# motion_sensor2.net
KiCad netlist of a schematic drawn in EasyEDA
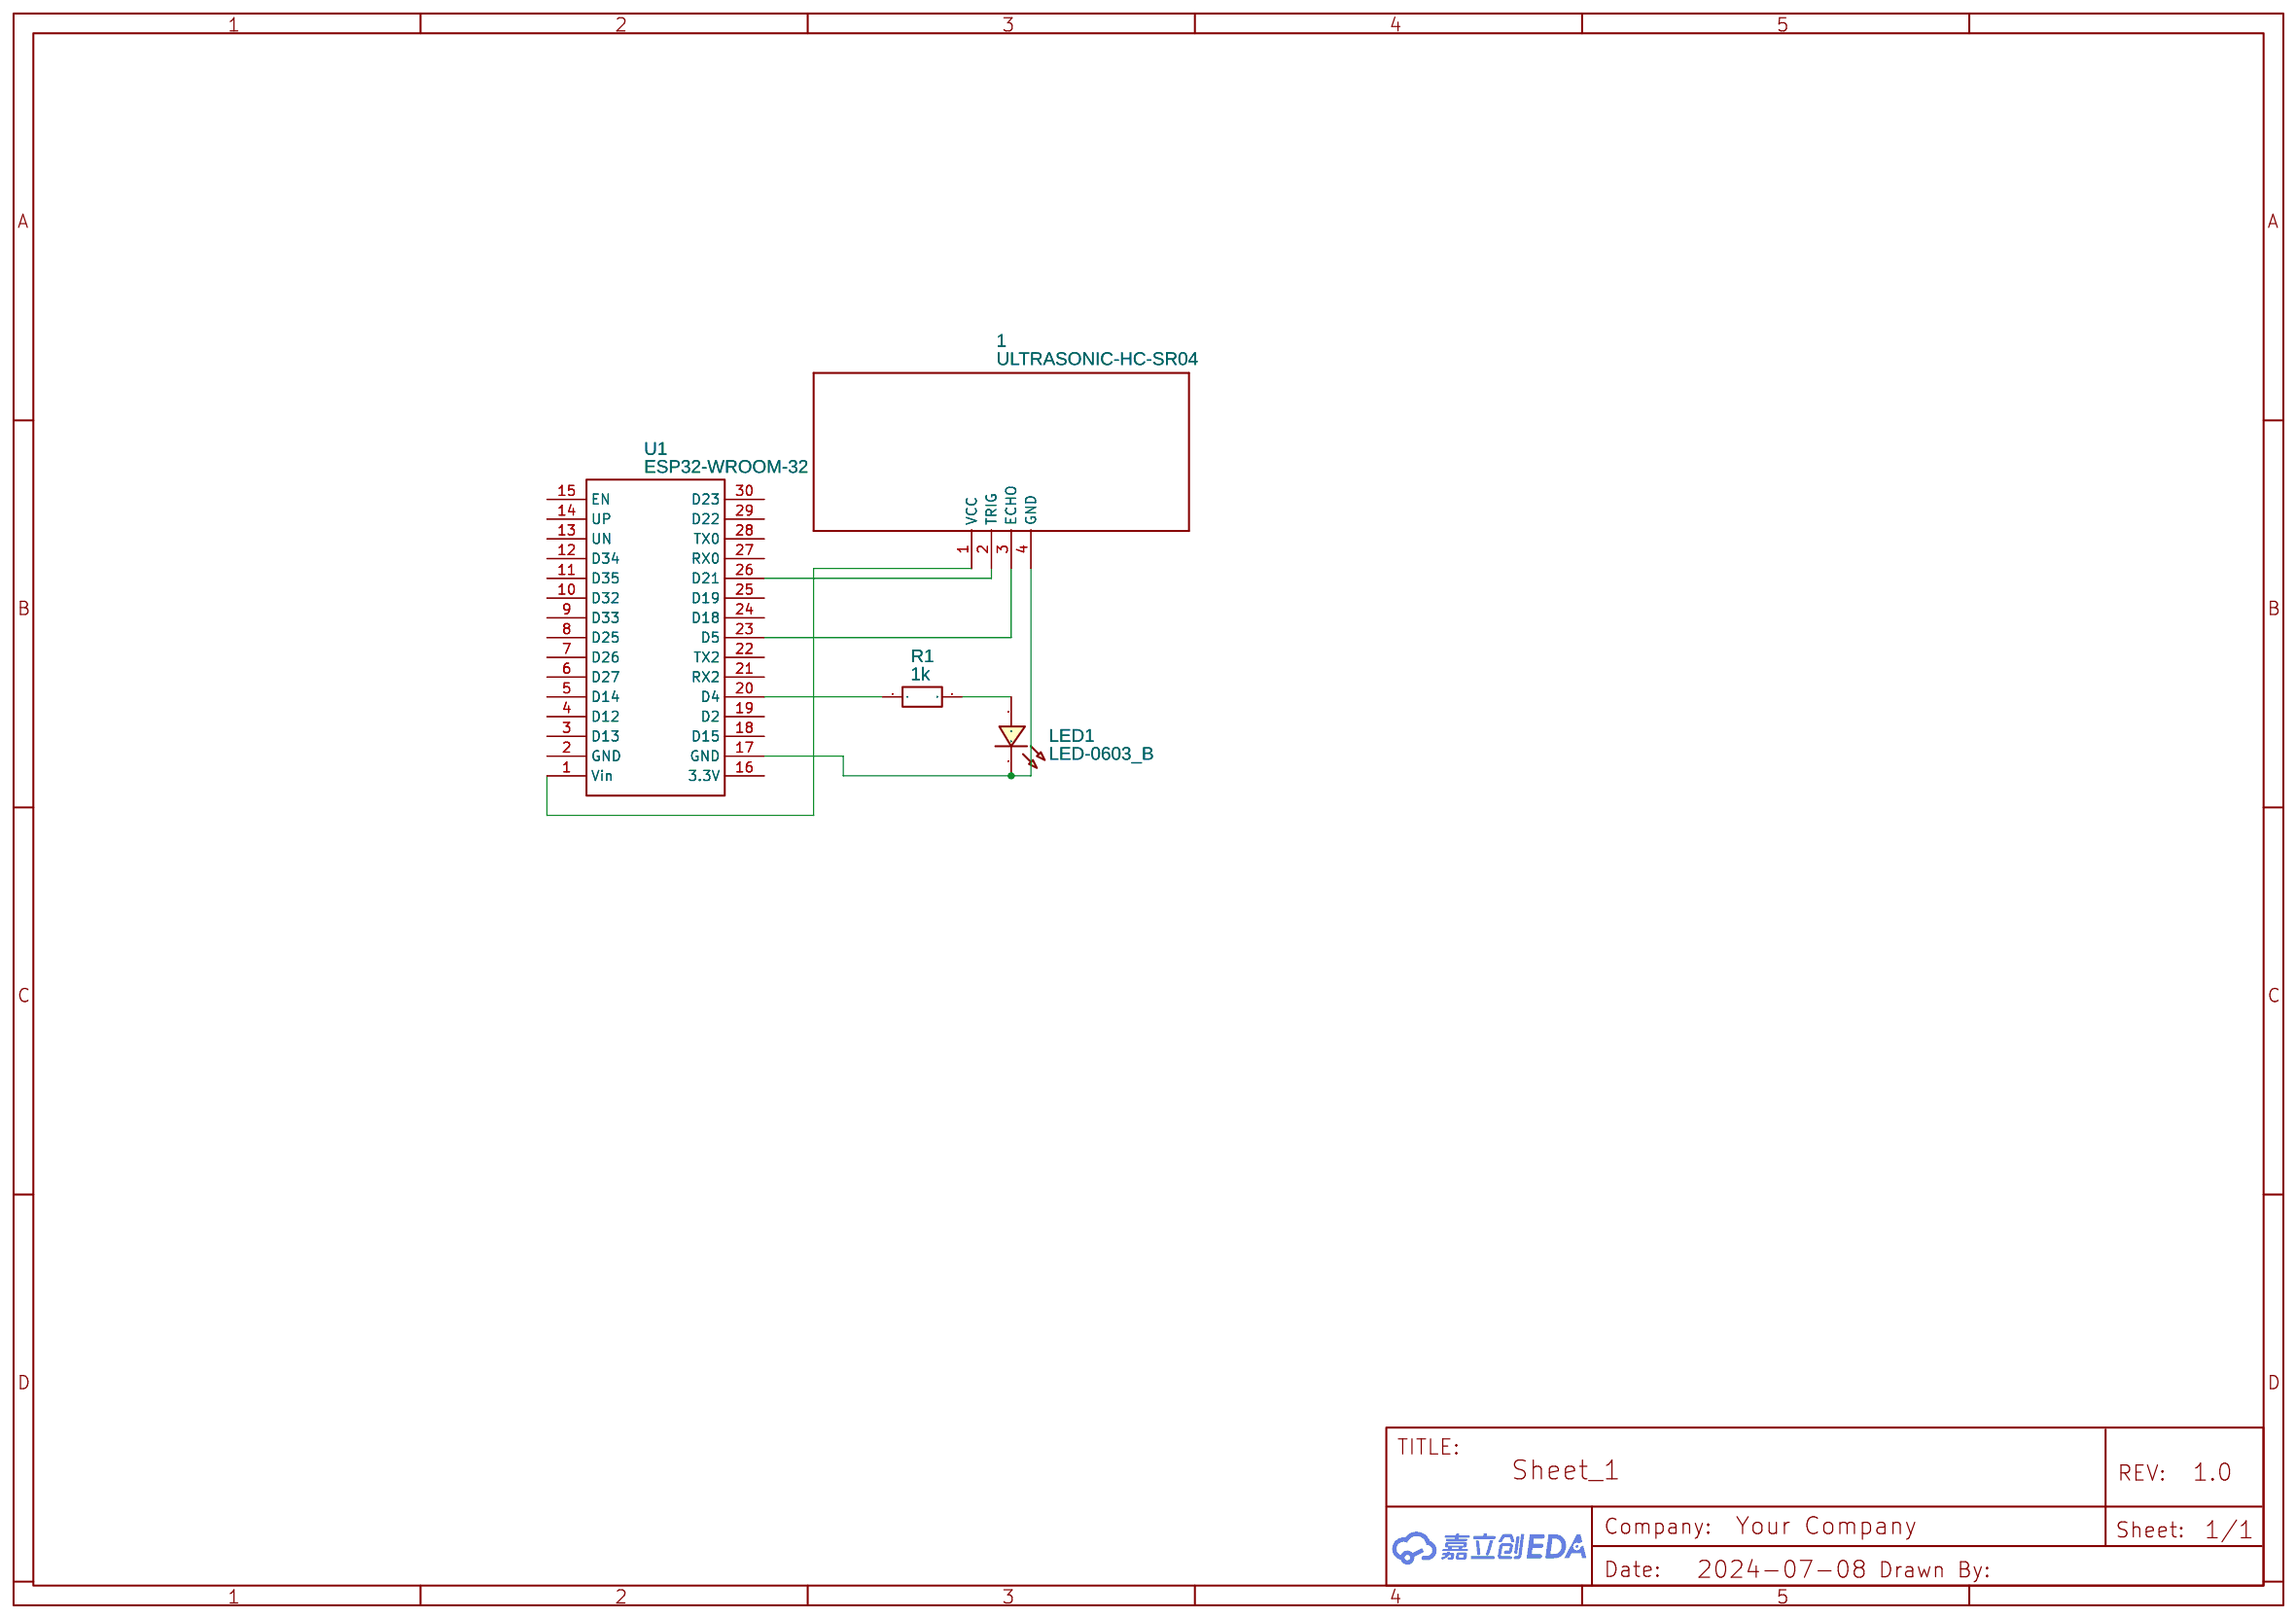
[diagram p0: schematic sheet]

(export (version "E")
  (design (tool "Eeschema 10.0.6"))
  (components
    (comp (ref "1") (value "ULTRASONIC-HC-SR04") (libsource (lib "") (part "ULTRASONIC-HC-SR04")))
    (comp (ref "LED1")
      (value "LED-0603_B")
      (fields
        (field (name "BOM_Manufacturer Part") "19-217/BHC-ZL1M2RY/3T")
        (field (name "BOM_Supplier Part") "C72041")
      )
      (libsource (lib "") (part "LED-0603_B"))
    )
    (comp (ref "R1") (value "1k") (libsource (lib "") (part "R_0603_EU")))
    (comp (ref "U1") (value "ESP32-WROOM-32") (libsource (lib "") (part "ESP32-WROOM-32")))
  )
  (nets
    (net (code "1") (name "Net-(1-ECHO)") (class "Default")
      (node (ref "1") (pin "3") (pinfunction "ECHO_3") (pintype "bidirectional"))
      (node (ref "U1") (pin "23") (pinfunction "D5_23") (pintype "unspecified"))
    )
    (net (code "2") (name "Net-(1-GND)") (class "Default")
      (node (ref "1") (pin "4") (pinfunction "GND_4") (pintype "bidirectional"))
      (node (ref "LED1") (pin "2") (pinfunction "2_2") (pintype "unspecified"))
      (node (ref "U1") (pin "17") (pinfunction "GND_17") (pintype "unspecified"))
    )
    (net (code "3") (name "Net-(1-TRIG)") (class "Default")
      (node (ref "1") (pin "2") (pinfunction "TRIG_2") (pintype "bidirectional"))
      (node (ref "U1") (pin "26") (pinfunction "D21_26") (pintype "unspecified"))
    )
    (net (code "4") (name "Net-(1-VCC)") (class "Default")
      (node (ref "1") (pin "1") (pinfunction "VCC_1") (pintype "bidirectional"))
      (node (ref "U1") (pin "1") (pinfunction "Vin_1") (pintype "unspecified"))
    )
    (net (code "5") (name "Net-(LED1-Pad1)") (class "Default")
      (node (ref "LED1") (pin "1") (pinfunction "1_1") (pintype "unspecified"))
      (node (ref "R1") (pin "2") (pinfunction "2_2") (pintype "unspecified"))
    )
    (net (code "6") (name "Net-(U1-D4)") (class "Default")
      (node (ref "R1") (pin "1") (pinfunction "1_1") (pintype "unspecified"))
      (node (ref "U1") (pin "20") (pinfunction "D4_20") (pintype "unspecified"))
    )
    (net (code "7") (name "unconnected-(U1-3.3V-Pad16)") (class "Default")
      (node (ref "U1") (pin "16") (pinfunction "3.3V_16") (pintype "unspecified"))
    )
    (net (code "8") (name "unconnected-(U1-D2-Pad19)") (class "Default")
      (node (ref "U1") (pin "19") (pinfunction "D2_19") (pintype "unspecified"))
    )
    (net (code "9") (name "unconnected-(U1-D12-Pad4)") (class "Default")
      (node (ref "U1") (pin "4") (pinfunction "D12_4") (pintype "unspecified"))
    )
    (net (code "10") (name "unconnected-(U1-D13-Pad3)") (class "Default")
      (node (ref "U1") (pin "3") (pinfunction "D13_3") (pintype "unspecified"))
    )
    (net (code "11") (name "unconnected-(U1-D14-Pad5)") (class "Default")
      (node (ref "U1") (pin "5") (pinfunction "D14_5") (pintype "unspecified"))
    )
    (net (code "12") (name "unconnected-(U1-D15-Pad18)") (class "Default")
      (node (ref "U1") (pin "18") (pinfunction "D15_18") (pintype "unspecified"))
    )
    (net (code "13") (name "unconnected-(U1-D18-Pad24)") (class "Default")
      (node (ref "U1") (pin "24") (pinfunction "D18_24") (pintype "unspecified"))
    )
    (net (code "14") (name "unconnected-(U1-D19-Pad25)") (class "Default")
      (node (ref "U1") (pin "25") (pinfunction "D19_25") (pintype "unspecified"))
    )
    (net (code "15") (name "unconnected-(U1-D22-Pad29)") (class "Default")
      (node (ref "U1") (pin "29") (pinfunction "D22_29") (pintype "unspecified"))
    )
    (net (code "16") (name "unconnected-(U1-D23-Pad30)") (class "Default")
      (node (ref "U1") (pin "30") (pinfunction "D23_30") (pintype "unspecified"))
    )
    (net (code "17") (name "unconnected-(U1-D25-Pad8)") (class "Default")
      (node (ref "U1") (pin "8") (pinfunction "D25_8") (pintype "unspecified"))
    )
    (net (code "18") (name "unconnected-(U1-D26-Pad7)") (class "Default")
      (node (ref "U1") (pin "7") (pinfunction "D26_7") (pintype "unspecified"))
    )
    (net (code "19") (name "unconnected-(U1-D27-Pad6)") (class "Default")
      (node (ref "U1") (pin "6") (pinfunction "D27_6") (pintype "unspecified"))
    )
    (net (code "20") (name "unconnected-(U1-D32-Pad10)") (class "Default")
      (node (ref "U1") (pin "10") (pinfunction "D32_10") (pintype "unspecified"))
    )
    (net (code "21") (name "unconnected-(U1-D33-Pad9)") (class "Default")
      (node (ref "U1") (pin "9") (pinfunction "D33_9") (pintype "unspecified"))
    )
    (net (code "22") (name "unconnected-(U1-D34-Pad12)") (class "Default")
      (node (ref "U1") (pin "12") (pinfunction "D34_12") (pintype "unspecified"))
    )
    (net (code "23") (name "unconnected-(U1-D35-Pad11)") (class "Default")
      (node (ref "U1") (pin "11") (pinfunction "D35_11") (pintype "unspecified"))
    )
    (net (code "24") (name "unconnected-(U1-EN-Pad15)") (class "Default")
      (node (ref "U1") (pin "15") (pinfunction "EN_15") (pintype "unspecified"))
    )
    (net (code "25") (name "unconnected-(U1-GND-Pad2)") (class "Default")
      (node (ref "U1") (pin "2") (pinfunction "GND_2") (pintype "unspecified"))
    )
    (net (code "26") (name "unconnected-(U1-RX0-Pad27)") (class "Default")
      (node (ref "U1") (pin "27") (pinfunction "RX0_27") (pintype "unspecified"))
    )
    (net (code "27") (name "unconnected-(U1-RX2-Pad21)") (class "Default")
      (node (ref "U1") (pin "21") (pinfunction "RX2_21") (pintype "unspecified"))
    )
    (net (code "28") (name "unconnected-(U1-TX0-Pad28)") (class "Default")
      (node (ref "U1") (pin "28") (pinfunction "TX0_28") (pintype "unspecified"))
    )
    (net (code "29") (name "unconnected-(U1-TX2-Pad22)") (class "Default")
      (node (ref "U1") (pin "22") (pinfunction "TX2_22") (pintype "unspecified"))
    )
    (net (code "30") (name "unconnected-(U1-UN-Pad13)") (class "Default")
      (node (ref "U1") (pin "13") (pinfunction "UN_13") (pintype "unspecified"))
    )
    (net (code "31") (name "unconnected-(U1-UP-Pad14)") (class "Default")
      (node (ref "U1") (pin "14") (pinfunction "UP_14") (pintype "unspecified"))
    )
  )
)
